# Battery_Management.net
KiCad netlist of a schematic drawn in Altium Designer
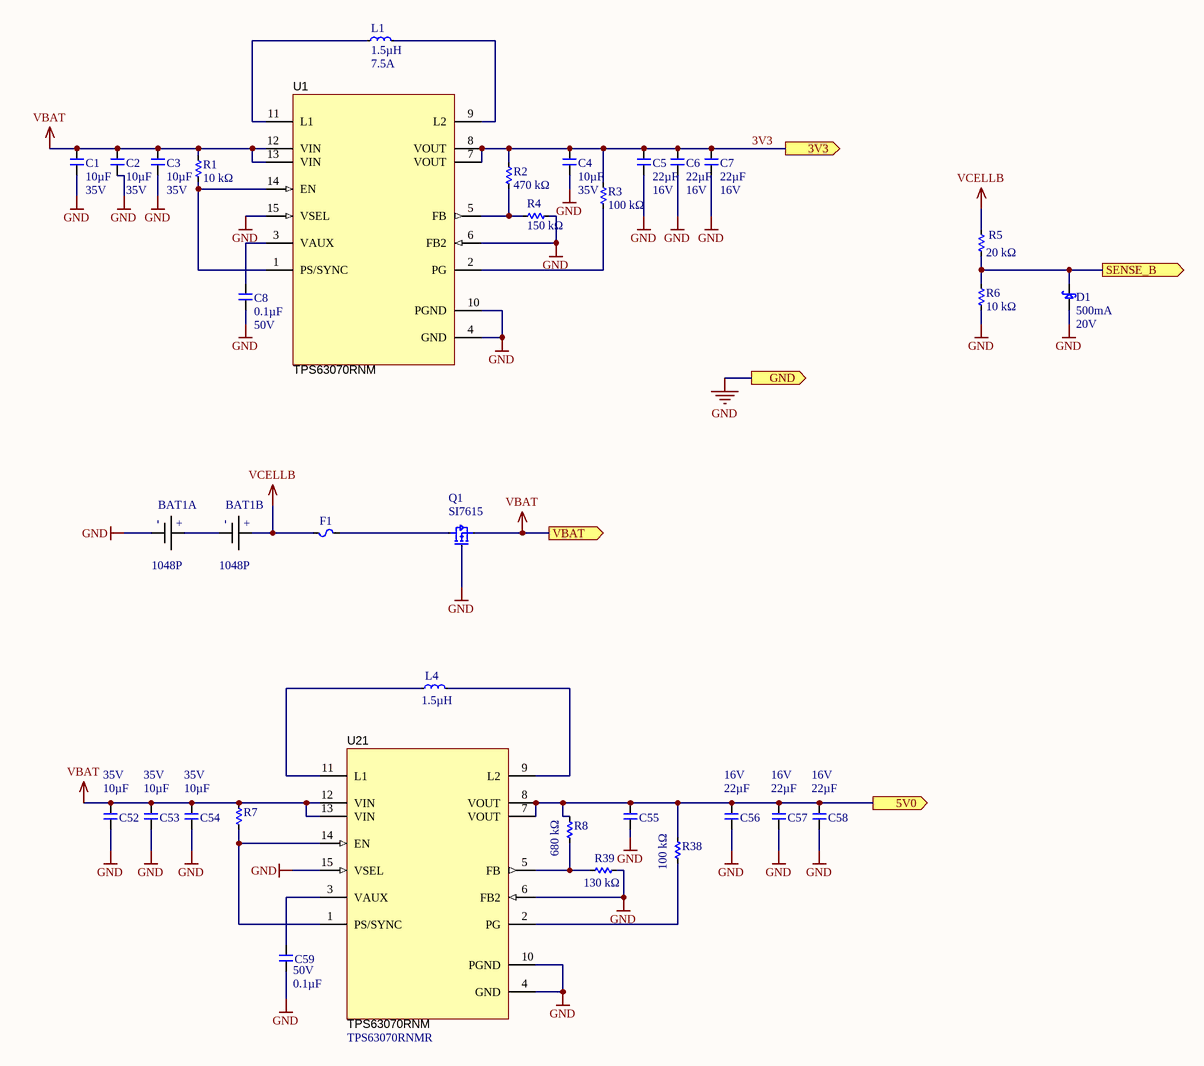
[diagram p0: Battery_Management.SchDoc]

(export (version "E")
  (design (tool "Eeschema 10.0.6"))
  (components
    (comp (ref "BAT1")
      (value "BATT_Clip_Li-Ion_2x")
      (footprint "BATT_18650_KEYSTONE_1048")
      (description "Dual Lithium Ion Cell Holder")
      (fields
        (field (name "MANUFACTURER PART NUMBER") "1048P")
        (field (name "MANUFACTURER") "Keystone Electronics")
      )
      (libsource (lib "Stanford Student Space Initiative") (part "BATT_Clip_Li-Ion_2x"))
    )
    (comp (ref "C1")
      (value "490-13248-1-ND")
      (footprint "C0603")
      (description "CAP CER 10UF 35V X5R 0603 20%")
      (fields
        (field (name "CAPACITANCE (SHORTHAND)") "10µF")
        (field (name "RATED VOLTAGE") "35V")
        (field (name "MANUFACTURER") "Murata Electronics North America")
      )
      (libsource (lib "Stanford Student Space Initiative") (part "__template_cap"))
    )
    (comp (ref "C2")
      (value "490-13248-1-ND")
      (footprint "C0603")
      (description "CAP CER 10UF 35V X5R 0603 20%")
      (fields
        (field (name "CAPACITANCE (SHORTHAND)") "10µF")
        (field (name "RATED VOLTAGE") "35V")
        (field (name "MANUFACTURER") "Murata Electronics North America")
      )
      (libsource (lib "Stanford Student Space Initiative") (part "__template_cap"))
    )
    (comp (ref "C3")
      (value "490-13248-1-ND")
      (footprint "C0603")
      (description "CAP CER 10UF 35V X5R 0603 20%")
      (fields
        (field (name "CAPACITANCE (SHORTHAND)") "10µF")
        (field (name "RATED VOLTAGE") "35V")
        (field (name "MANUFACTURER") "Murata Electronics North America")
      )
      (libsource (lib "Stanford Student Space Initiative") (part "__template_cap"))
    )
    (comp (ref "C4")
      (value "490-13248-1-ND")
      (footprint "C0603")
      (description "CAP CER 10UF 35V X5R 0603 20%")
      (fields
        (field (name "CAPACITANCE (SHORTHAND)") "10µF")
        (field (name "RATED VOLTAGE") "35V")
        (field (name "MANUFACTURER") "Murata Electronics North America")
      )
      (libsource (lib "Stanford Student Space Initiative") (part "__template_cap"))
    )
    (comp (ref "C5")
      (value "1276-7076-1-ND")
      (footprint "C0603")
      (description "CAP CER 22UF 16V X5R 0603 20%")
      (fields
        (field (name "CAPACITANCE (SHORTHAND)") "22µF")
        (field (name "RATED VOLTAGE") "16V")
        (field (name "MANUFACTURER") "Samsung Electro-Mechanics")
      )
      (libsource (lib "Stanford Student Space Initiative") (part "__template_cap"))
    )
    (comp (ref "C6")
      (value "1276-7076-1-ND")
      (footprint "C0603")
      (description "CAP CER 22UF 16V X5R 0603 20%")
      (fields
        (field (name "CAPACITANCE (SHORTHAND)") "22µF")
        (field (name "RATED VOLTAGE") "16V")
        (field (name "MANUFACTURER") "Samsung Electro-Mechanics")
      )
      (libsource (lib "Stanford Student Space Initiative") (part "__template_cap"))
    )
    (comp (ref "C7")
      (value "1276-7076-1-ND")
      (footprint "C0603")
      (description "CAP CER 22UF 16V X5R 0603 20%")
      (fields
        (field (name "CAPACITANCE (SHORTHAND)") "22µF")
        (field (name "RATED VOLTAGE") "16V")
        (field (name "MANUFACTURER") "Samsung Electro-Mechanics")
      )
      (libsource (lib "Stanford Student Space Initiative") (part "__template_cap"))
    )
    (comp (ref "C8")
      (value "490-1519-1-ND")
      (footprint "C0603")
      (description "CAP CER 0603 0.1µF X7R 50V 10%")
      (fields
        (field (name "CAPACITANCE (SHORTHAND)") "0.1µF")
        (field (name "RATED VOLTAGE") "50V")
        (field (name "MANUFACTURER") "Murata Electronics North America")
      )
      (libsource (lib "Stanford Student Space Initiative") (part "__template_cap"))
    )
    (comp (ref "C52")
      (value "490-13248-1-ND")
      (footprint "C0603")
      (description "CAP CER 10UF 35V X5R 0603 20%")
      (fields
        (field (name "RATED VOLTAGE") "35V")
        (field (name "CAPACITANCE (SHORTHAND)") "10µF")
        (field (name "MANUFACTURER") "Murata Electronics North America")
      )
      (libsource (lib "Stanford Student Space Initiative") (part "__template_cap"))
    )
    (comp (ref "C53")
      (value "490-13248-1-ND")
      (footprint "C0603")
      (description "CAP CER 10UF 35V X5R 0603 20%")
      (fields
        (field (name "RATED VOLTAGE") "35V")
        (field (name "CAPACITANCE (SHORTHAND)") "10µF")
        (field (name "MANUFACTURER") "Murata Electronics North America")
      )
      (libsource (lib "Stanford Student Space Initiative") (part "__template_cap"))
    )
    (comp (ref "C54")
      (value "490-13248-1-ND")
      (footprint "C0603")
      (description "CAP CER 10UF 35V X5R 0603 20%")
      (fields
        (field (name "RATED VOLTAGE") "35V")
        (field (name "CAPACITANCE (SHORTHAND)") "10µF")
        (field (name "MANUFACTURER") "Murata Electronics North America")
      )
      (libsource (lib "Stanford Student Space Initiative") (part "__template_cap"))
    )
    (comp (ref "C55")
      (value "490-13248-1-ND")
      (footprint "C0603")
      (description "CAP CER 10UF 35V X5R 0603 20%")
      (fields (field (name "MANUFACTURER") "Murata Electronics North America"))
      (libsource (lib "Stanford Student Space Initiative") (part "__template_cap"))
    )
    (comp (ref "C56")
      (value "1276-7076-1-ND")
      (footprint "C0603")
      (description "CAP CER 22UF 16V X5R 0603 20%")
      (fields
        (field (name "RATED VOLTAGE") "16V")
        (field (name "MANUFACTURER") "Samsung Electro-Mechanics")
        (field (name "CAPACITANCE (SHORTHAND)") "22µF")
      )
      (libsource (lib "Stanford Student Space Initiative") (part "__template_cap"))
    )
    (comp (ref "C57")
      (value "1276-7076-1-ND")
      (footprint "C0603")
      (description "CAP CER 22UF 16V X5R 0603 20%")
      (fields
        (field (name "RATED VOLTAGE") "16V")
        (field (name "MANUFACTURER") "Samsung Electro-Mechanics")
        (field (name "CAPACITANCE (SHORTHAND)") "22µF")
      )
      (libsource (lib "Stanford Student Space Initiative") (part "__template_cap"))
    )
    (comp (ref "C58")
      (value "1276-7076-1-ND")
      (footprint "C0603")
      (description "CAP CER 22UF 16V X5R 0603 20%")
      (fields
        (field (name "RATED VOLTAGE") "16V")
        (field (name "MANUFACTURER") "Samsung Electro-Mechanics")
        (field (name "CAPACITANCE (SHORTHAND)") "22µF")
      )
      (libsource (lib "Stanford Student Space Initiative") (part "__template_cap"))
    )
    (comp (ref "C59")
      (value "490-1519-1-ND")
      (footprint "C0603")
      (description "CAP CER 0603 0.1µF X7R 50V 10%")
      (fields
        (field (name "MANUFACTURER") "Murata Electronics North America")
        (field (name "CAPACITANCE (SHORTHAND)") "0.1µF")
        (field (name "RATED VOLTAGE") "50V")
      )
      (libsource (lib "Stanford Student Space Initiative") (part "__template_cap"))
    )
    (comp (ref "D1")
      (value "SCHOTTKY_MBR0520L")
      (footprint "SOD123")
      (description "DIODE SCHOTTKY 0.5A 20V SOD-123")
      (fields
        (field (name "MANUFACTURER") "Fairchild Semiconductor")
        (field (name "MANUFACTURER PART NUMBER") "MBR0520L")
        (field (name "CURRENT - AVERAGE RECTIFIED (IO)") "500mA")
        (field (name "VOLTAGE - DC REVERSE (VR) (MAX)") "20V")
      )
      (libsource (lib "") (part "Symbol_2"))
    )
    (comp (ref "F1")
      (value "__template_fuse")
      (footprint "R1206")
      (libsource (lib "Stanford Student Space Initiative") (part "Symbol"))
    )
    (comp (ref "L1")
      (value "Symbol")
      (footprint "SMD5230")
      (description "INDUCTOR POWER 1.5UH 7.5A SMD")
      (fields
        (field (name "MANUFACTURER") "Vishay Dale")
        (field (name "MANUFACTURER PART NUMBER") "IHLP2020CZER1R5M11")
        (field (name "INDUCTANCE") "1.5µH")
        (field (name "CURRENT RATING") "7.5A")
      )
      (libsource (lib "") (part "Symbol_1"))
    )
    (comp (ref "L4")
      (value "IND_IHLP2020CZER1R5M11")
      (footprint "SMD5230")
      (description "INDUCTOR POWER 1.5UH 7.5A SMD")
      (fields
        (field (name "INDUCTANCE") "1.5µH")
        (field (name "TOLERANCE") "±20%")
        (field (name "MANUFACTURER PART NUMBER") "IHLP2020CZER1R5M11")
      )
      (libsource (lib "") (part "Symbol_1"))
    )
    (comp (ref "Q1")
      (value "SI7615")
      (footprint "POWERPAK_1212-8_SINGLE")
      (description "MOSFET P-CH 20V 35A PPK")
      (fields
        (field (name "MANUFACTURER") "Vishay Siliconix")
        (field (name "MANUFACTURER PART NUMBER") "SI7615ADN-T1-GE3")
      )
      (libsource (lib "Stanford Student Space Initiative") (part "PFET_SI7615ADN-T1"))
    )
    (comp (ref "R1")
      (value "311-10.0KHRCT-ND")
      (footprint "R0603")
      (description "RES SMD 10K OHM 1% 1/10W 0603")
      (fields
        (field (name "RESISTANCE") "10 kΩ")
        (field (name "MANUFACTURER PART NUMBER") "RC0603FR-0710KL")
        (field (name "MANUFACTURER") "Yageo")
      )
      (libsource (lib "Stanford Student Space Initiative") (part "__template_resistor"))
    )
    (comp (ref "R2")
      (value "311-470KHRCT-ND")
      (footprint "R0603")
      (description "RES SMD 470K OHM 1% 1/10W 0603")
      (fields
        (field (name "MANUFACTURER PART NUMBER") "RC0603FR-07470KL")
        (field (name "MANUFACTURER") "Yageo")
        (field (name "RESISTANCE") "470 kΩ")
      )
      (libsource (lib "Stanford Student Space Initiative") (part "__template_resistor"))
    )
    (comp (ref "R3")
      (value "311-100KHRCT-ND")
      (footprint "R0603")
      (description "RES SMD 100K OHM 1% 1/10W 0603")
      (fields
        (field (name "MANUFACTURER PART NUMBER") "RC0603FR-07100KL")
        (field (name "MANUFACTURER") "Yageo")
        (field (name "RESISTANCE") "100 kΩ")
      )
      (libsource (lib "Stanford Student Space Initiative") (part "__template_resistor"))
    )
    (comp (ref "R4")
      (value "311-150KHRCT-ND")
      (footprint "R0603")
      (description "RES SMD 150K OHM 1% 1/10W 0603")
      (fields
        (field (name "MANUFACTURER PART NUMBER") "RC0603FR-07150KL")
        (field (name "MANUFACTURER") "Yageo")
        (field (name "RESISTANCE") "150 kΩ")
      )
      (libsource (lib "Stanford Student Space Initiative") (part "__template_resistor"))
    )
    (comp (ref "R5")
      (value "311-20.0KHRCT-ND")
      (footprint "R0603")
      (description "RES SMD 20K OHM 1% 1/10W 0603")
      (fields
        (field (name "RESISTANCE") "20 kΩ")
        (field (name "MANUFACTURER PART NUMBER") "RC0603FR-0720KL")
        (field (name "MANUFACTURER") "Yageo")
      )
      (libsource (lib "Stanford Student Space Initiative") (part "__template_resistor"))
    )
    (comp (ref "R6")
      (value "311-10.0KHRCT-ND")
      (footprint "R0603")
      (description "RES SMD 10K OHM 1% 1/10W 0603")
      (fields
        (field (name "RESISTANCE") "10 kΩ")
        (field (name "MANUFACTURER PART NUMBER") "RC0603FR-0710KL")
        (field (name "MANUFACTURER") "Yageo")
      )
      (libsource (lib "Stanford Student Space Initiative") (part "__template_resistor"))
    )
    (comp (ref "R7")
      (value "311-10.0KHRCT-ND")
      (footprint "R0603")
      (description "RES SMD 10K OHM 1% 1/10W 0603")
      (fields
        (field (name "MANUFACTURER") "Yageo")
        (field (name "MANUFACTURER PART NUMBER") "RC0603FR-0710KL")
      )
      (libsource (lib "Stanford Student Space Initiative") (part "__template_resistor"))
    )
    (comp (ref "R8")
      (value "311-680KHRCT-ND")
      (footprint "R0603")
      (description "RES SMD 680K OHM 1% 1/10W 0603")
      (fields
        (field (name "TOLERANCE") "±1%")
        (field (name "RESISTANCE") "680 kΩ")
        (field (name "MANUFACTURER") "Yageo")
      )
      (libsource (lib "Stanford Student Space Initiative") (part "__template_resistor"))
    )
    (comp (ref "R38")
      (value "311-100KHRCT-ND")
      (footprint "R0603")
      (description "RES SMD 100K OHM 1% 1/10W 0603")
      (fields
        (field (name "MANUFACTURER") "Yageo")
        (field (name "MANUFACTURER PART NUMBER") "RC0603FR-07100KL")
        (field (name "RESISTANCE") "100 kΩ")
      )
      (libsource (lib "Stanford Student Space Initiative") (part "__template_resistor"))
    )
    (comp (ref "R39")
      (value "311-130KHRCT-ND")
      (footprint "R0603")
      (description "RES SMD 130K OHM 1% 1/10W 0603")
      (fields
        (field (name "MANUFACTURER PART NUMBER") "RC0603FR-07130KL")
        (field (name "TOLERANCE") "±1%")
        (field (name "RESISTANCE") "130 kΩ")
      )
      (libsource (lib "Stanford Student Space Initiative") (part "__template_resistor"))
    )
    (comp (ref "U1")
      (value "TPS63070RNM")
      (footprint "TPS63070")
      (description "BUCKBOOST TPS63070RNM, RNM0015A")
      (fields
        (field (name "MANUFACTURER") "Texas Instruments")
        (field (name "MANUFACTURER PART NUMBER") "TPS63070RNMR")
      )
      (libsource (lib "Stanford Student Space Initiative") (part "TPS63070RNM"))
    )
    (comp (ref "U21")
      (value "TPS63070RNM")
      (footprint "TPS63070")
      (description "BUCKBOOST TPS63070RNM, RNM0015A")
      (fields
        (field (name "MANUFACTURER PART NUMBER") "TPS63070RNMR")
        (field (name "MANUFACTURER") "Texas Instruments")
      )
      (libsource (lib "Stanford Student Space Initiative") (part "TPS63070RNM"))
    )
  )
  (nets
    (net (code "1") (name "/3V3") (class "Default")
      (node (ref "C4") (pin "1") (pintype "passive"))
      (node (ref "C5") (pin "1") (pintype "passive"))
      (node (ref "C6") (pin "1") (pintype "passive"))
      (node (ref "C7") (pin "1") (pintype "passive"))
      (node (ref "R2") (pin "2") (pinfunction "2_2") (pintype "passive"))
      (node (ref "R3") (pin "2") (pinfunction "2_2") (pintype "passive"))
      (node (ref "U1") (pin "7") (pinfunction "VOUT_7") (pintype "power_in"))
      (node (ref "U1") (pin "8") (pinfunction "VOUT_8") (pintype "power_in"))
    )
    (net (code "2") (name "/5V0") (class "Default")
      (node (ref "C55") (pin "1") (pintype "passive"))
      (node (ref "C56") (pin "1") (pintype "passive"))
      (node (ref "C57") (pin "1") (pintype "passive"))
      (node (ref "C58") (pin "1") (pintype "passive"))
      (node (ref "R38") (pin "2") (pinfunction "2_2") (pintype "passive"))
      (node (ref "R8") (pin "2") (pinfunction "2_2") (pintype "passive"))
      (node (ref "U21") (pin "7") (pinfunction "VOUT_7") (pintype "power_in"))
      (node (ref "U21") (pin "8") (pinfunction "VOUT_8") (pintype "power_in"))
    )
    (net (code "3") (name "/SENSE_B") (class "Default")
      (node (ref "D1") (pin "2") (pintype "passive"))
      (node (ref "R5") (pin "1") (pinfunction "1_1") (pintype "passive"))
      (node (ref "R6") (pin "2") (pinfunction "2_2") (pintype "passive"))
    )
    (net (code "4") (name "GND") (class "Default")
      (node (ref "BAT1") (pin "CELL1-") (pinfunction "CELL1-_CELL1-") (pintype "passive"))
      (node (ref "C1") (pin "2") (pintype "passive"))
      (node (ref "C2") (pin "2") (pintype "passive"))
      (node (ref "C3") (pin "2") (pintype "passive"))
      (node (ref "C4") (pin "2") (pintype "passive"))
      (node (ref "C5") (pin "2") (pintype "passive"))
      (node (ref "C52") (pin "2") (pintype "passive"))
      (node (ref "C53") (pin "2") (pintype "passive"))
      (node (ref "C54") (pin "2") (pintype "passive"))
      (node (ref "C55") (pin "2") (pintype "passive"))
      (node (ref "C56") (pin "2") (pintype "passive"))
      (node (ref "C57") (pin "2") (pintype "passive"))
      (node (ref "C58") (pin "2") (pintype "passive"))
      (node (ref "C59") (pin "2") (pintype "passive"))
      (node (ref "C6") (pin "2") (pintype "passive"))
      (node (ref "C7") (pin "2") (pintype "passive"))
      (node (ref "C8") (pin "2") (pintype "passive"))
      (node (ref "D1") (pin "1") (pintype "passive"))
      (node (ref "Q1") (pin "4") (pintype "passive"))
      (node (ref "R39") (pin "2") (pinfunction "2_2") (pintype "passive"))
      (node (ref "R4") (pin "2") (pinfunction "2_2") (pintype "passive"))
      (node (ref "R6") (pin "1") (pinfunction "1_1") (pintype "passive"))
      (node (ref "U1") (pin "10") (pinfunction "PGND_10") (pintype "power_in"))
      (node (ref "U1") (pin "15") (pinfunction "VSEL_15") (pintype "input"))
      (node (ref "U1") (pin "4") (pinfunction "GND_4") (pintype "power_in"))
      (node (ref "U1") (pin "6") (pinfunction "FB2_6") (pintype "input"))
      (node (ref "U21") (pin "10") (pinfunction "PGND_10") (pintype "power_in"))
      (node (ref "U21") (pin "15") (pinfunction "VSEL_15") (pintype "input"))
      (node (ref "U21") (pin "4") (pinfunction "GND_4") (pintype "power_in"))
      (node (ref "U21") (pin "6") (pinfunction "FB2_6") (pintype "input"))
    )
    (net (code "5") (name "Net-(BAT1-PadCELL1+)") (class "Default")
      (node (ref "BAT1") (pin "CELL1+") (pinfunction "CELL1+_CELL1+") (pintype "passive"))
      (node (ref "BAT1") (pin "CELL2-") (pinfunction "CELL2-_CELL2-") (pintype "passive"))
    )
    (net (code "6") (name "Net-(F1-Pad2)") (class "Default")
      (node (ref "F1") (pin "2") (pintype "passive"))
      (node (ref "Q1") (pin "5") (pintype "passive"))
    )
    (net (code "7") (name "Net-(U1-EN)") (class "Default")
      (node (ref "R1") (pin "1") (pinfunction "1_1") (pintype "passive"))
      (node (ref "U1") (pin "1") (pinfunction "PS/SYNC_1") (pintype "passive"))
      (node (ref "U1") (pin "14") (pinfunction "EN_14") (pintype "input"))
    )
    (net (code "8") (name "Net-(U1-FB)") (class "Default")
      (node (ref "R2") (pin "1") (pinfunction "1_1") (pintype "passive"))
      (node (ref "R4") (pin "1") (pinfunction "1_1") (pintype "passive"))
      (node (ref "U1") (pin "5") (pinfunction "FB_5") (pintype "output"))
    )
    (net (code "9") (name "Net-(U1-L1)") (class "Default")
      (node (ref "L1") (pin "1") (pintype "passive"))
      (node (ref "U1") (pin "11") (pinfunction "L1_11") (pintype "passive"))
    )
    (net (code "10") (name "Net-(U1-L2)") (class "Default")
      (node (ref "L1") (pin "2") (pintype "passive"))
      (node (ref "U1") (pin "9") (pinfunction "L2_9") (pintype "passive"))
    )
    (net (code "11") (name "Net-(U1-PG)") (class "Default")
      (node (ref "R3") (pin "1") (pinfunction "1_1") (pintype "passive"))
      (node (ref "U1") (pin "2") (pinfunction "PG_2") (pintype "open_collector"))
    )
    (net (code "12") (name "Net-(U1-VAUX)") (class "Default")
      (node (ref "C8") (pin "1") (pintype "passive"))
      (node (ref "U1") (pin "3") (pinfunction "VAUX_3") (pintype "passive"))
    )
    (net (code "13") (name "Net-(U21-EN)") (class "Default")
      (node (ref "R7") (pin "1") (pinfunction "1_1") (pintype "passive"))
      (node (ref "U21") (pin "1") (pinfunction "PS/SYNC_1") (pintype "passive"))
      (node (ref "U21") (pin "14") (pinfunction "EN_14") (pintype "input"))
    )
    (net (code "14") (name "Net-(U21-FB)") (class "Default")
      (node (ref "R39") (pin "1") (pinfunction "1_1") (pintype "passive"))
      (node (ref "R8") (pin "1") (pinfunction "1_1") (pintype "passive"))
      (node (ref "U21") (pin "5") (pinfunction "FB_5") (pintype "output"))
    )
    (net (code "15") (name "Net-(U21-L1)") (class "Default")
      (node (ref "L4") (pin "1") (pintype "passive"))
      (node (ref "U21") (pin "11") (pinfunction "L1_11") (pintype "passive"))
    )
    (net (code "16") (name "Net-(U21-L2)") (class "Default")
      (node (ref "L4") (pin "2") (pintype "passive"))
      (node (ref "U21") (pin "9") (pinfunction "L2_9") (pintype "passive"))
    )
    (net (code "17") (name "Net-(U21-PG)") (class "Default")
      (node (ref "R38") (pin "1") (pinfunction "1_1") (pintype "passive"))
      (node (ref "U21") (pin "2") (pinfunction "PG_2") (pintype "open_collector"))
    )
    (net (code "18") (name "Net-(U21-VAUX)") (class "Default")
      (node (ref "C59") (pin "1") (pintype "passive"))
      (node (ref "U21") (pin "3") (pinfunction "VAUX_3") (pintype "passive"))
    )
    (net (code "19") (name "VBAT") (class "Default")
      (node (ref "C1") (pin "1") (pintype "passive"))
      (node (ref "C2") (pin "1") (pintype "passive"))
      (node (ref "C3") (pin "1") (pintype "passive"))
      (node (ref "C52") (pin "1") (pintype "passive"))
      (node (ref "C53") (pin "1") (pintype "passive"))
      (node (ref "C54") (pin "1") (pintype "passive"))
      (node (ref "Q1") (pin "1") (pintype "passive"))
      (node (ref "R1") (pin "2") (pinfunction "2_2") (pintype "passive"))
      (node (ref "R7") (pin "2") (pinfunction "2_2") (pintype "passive"))
      (node (ref "U1") (pin "12") (pinfunction "VIN_12") (pintype "power_in"))
      (node (ref "U1") (pin "13") (pinfunction "VIN_13") (pintype "power_in"))
      (node (ref "U21") (pin "12") (pinfunction "VIN_12") (pintype "power_in"))
      (node (ref "U21") (pin "13") (pinfunction "VIN_13") (pintype "power_in"))
    )
    (net (code "20") (name "VCELLB") (class "Default")
      (node (ref "BAT1") (pin "CELL2+") (pinfunction "CELL2+_CELL2+") (pintype "passive"))
      (node (ref "F1") (pin "1") (pintype "passive"))
      (node (ref "R5") (pin "2") (pinfunction "2_2") (pintype "passive"))
    )
  )
)
